# Dashboard.net
KiCad netlist of a schematic drawn in Altium Designer
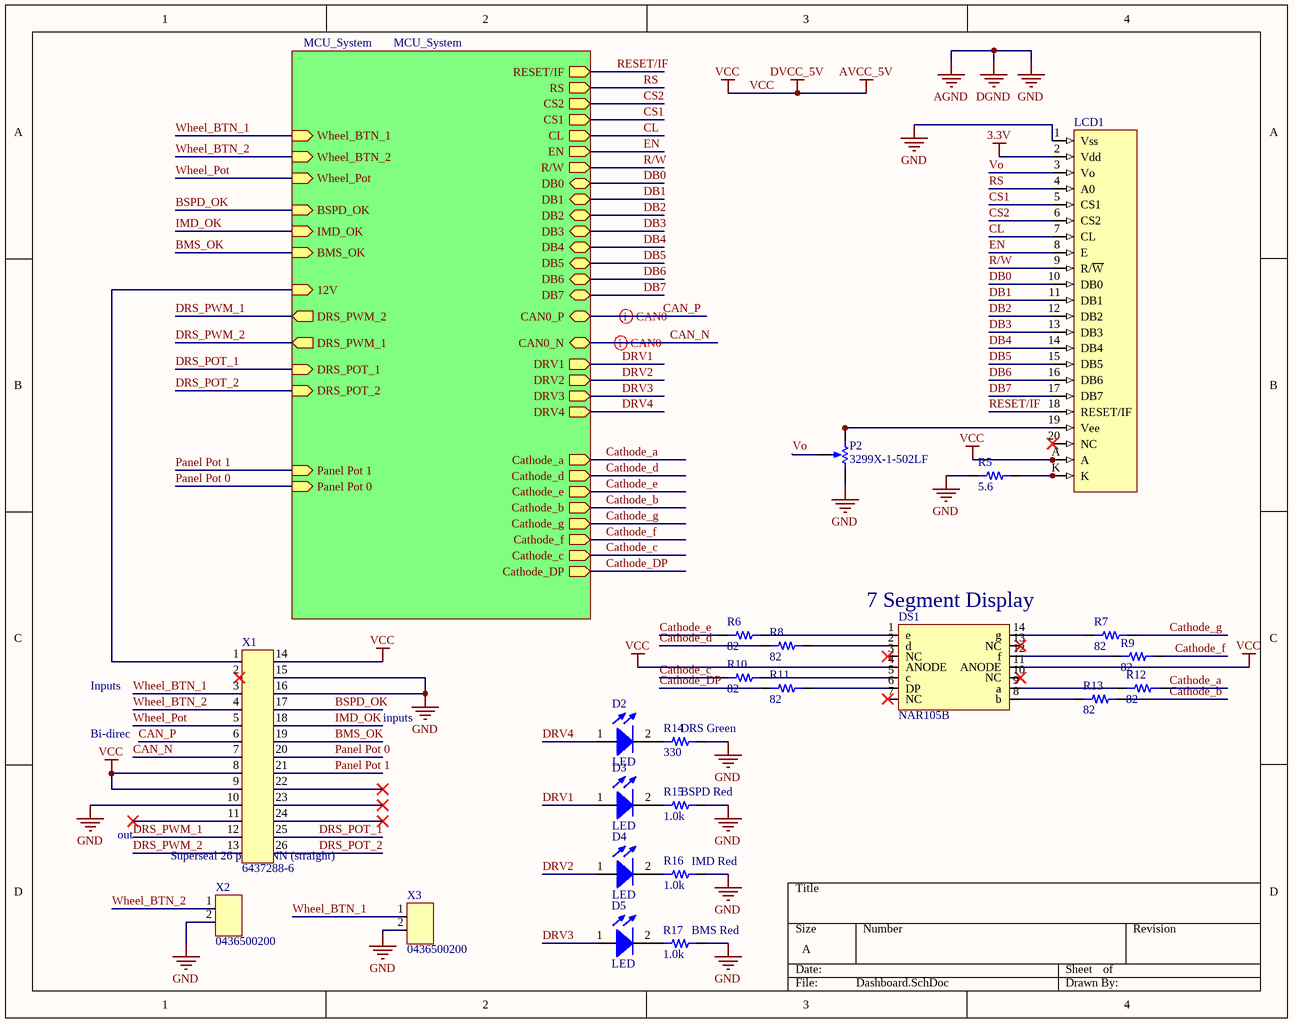
[diagram p0: Dashboard.SchDoc]

(export (version "E")
  (design (tool "Eeschema 10.0.6"))
  (components
    (comp (ref "D2")
      (value "LED")
      (footprint "LED TH")
      (description "LED GREEN DIFFUSED T/H")
      (fields (field (name "MFRPARTNO") "LTL-10233W"))
      (libsource (lib "Altium-Lib") (part "LED"))
    )
    (comp (ref "D3")
      (value "LED")
      (footprint "LED TH")
      (description "LED RED DIFFUSED T/H")
      (fields (field (name "MFRPARTNO") "LTL2R3KRD-EM"))
      (libsource (lib "Altium-Lib") (part "LED"))
    )
    (comp (ref "D4")
      (value "LED")
      (footprint "LED TH")
      (description "LED RED DIFFUSED T/H")
      (fields (field (name "MFRPARTNO") "LTL2R3KRD-EM"))
      (libsource (lib "Altium-Lib") (part "LED"))
    )
    (comp (ref "D5")
      (value "LED")
      (footprint "LED TH")
      (description "LED RED DIFFUSED T/H")
      (fields (field (name "MFRPARTNO") "LTL2R3KRD-EM"))
      (libsource (lib "Altium-Lib") (part "LED"))
    )
    (comp (ref "DS1")
      (value "NAR105B")
      (footprint "Stanley7Seg")
      (libsource (lib "Altium-Lib") (part "Stanley7Seg"))
    )
    (comp (ref "LCD1")
      (value "~")
      (footprint "NHD-12232")
      (fields (field (name "MFRPARTNO") "NHD-12232WG-EYYH-V#A-ND"))
      (libsource (lib "Altium-Lib") (part "NHD-12232"))
    )
    (comp (ref "P2")
      (value "3299X-1-502LF")
      (footprint "3299X-1-502LF")
      (libsource (lib "Altium-Lib") (part "3299X-1-502LF"))
    )
    (comp (ref "R5")
      (value "5.6")
      (footprint "RES 0805/2012")
      (fields
        (field (name "TOLERANCE") "1%")
        (field (name "POWER") "1/2W")
        (field (name "Comment") "Resistor 5.6 0805 1/2W 1%")
        (field (name "CREATED_BY") "Nick Mah")
      )
      (libsource (lib "Altium-Lib") (part "Resistor"))
    )
    (comp (ref "R6")
      (value "82")
      (footprint "RES 0805/2012")
      (fields
        (field (name "TOLERANCE") "5%")
        (field (name "POWER") "1/4W")
        (field (name "Comment") "Resistor 82 0805 1/4W 5%")
        (field (name "CREATED_BY") "Nick Mah")
      )
      (libsource (lib "Altium-Lib") (part "Resistor"))
    )
    (comp (ref "R7")
      (value "82")
      (footprint "RES 0805/2012")
      (fields
        (field (name "TOLERANCE") "5%")
        (field (name "POWER") "1/4W")
        (field (name "Comment") "Resistor 82 0805 1/4W 5%")
        (field (name "CREATED_BY") "Nick Mah")
      )
      (libsource (lib "Altium-Lib") (part "Resistor"))
    )
    (comp (ref "R8")
      (value "82")
      (footprint "RES 0805/2012")
      (fields
        (field (name "TOLERANCE") "5%")
        (field (name "POWER") "1/4W")
        (field (name "Comment") "Resistor 82 0805 1/4W 5%")
        (field (name "CREATED_BY") "Nick Mah")
      )
      (libsource (lib "Altium-Lib") (part "Resistor"))
    )
    (comp (ref "R9")
      (value "82")
      (footprint "RES 0805/2012")
      (fields
        (field (name "TOLERANCE") "5%")
        (field (name "POWER") "1/4W")
        (field (name "Comment") "Resistor 82 0805 1/4W 5%")
        (field (name "CREATED_BY") "Nick Mah")
      )
      (libsource (lib "Altium-Lib") (part "Resistor"))
    )
    (comp (ref "R10")
      (value "82")
      (footprint "RES 0805/2012")
      (fields
        (field (name "TOLERANCE") "5%")
        (field (name "POWER") "1/4W")
        (field (name "Comment") "Resistor 82 0805 1/4W 5%")
        (field (name "CREATED_BY") "Nick Mah")
      )
      (libsource (lib "Altium-Lib") (part "Resistor"))
    )
    (comp (ref "R11")
      (value "82")
      (footprint "RES 0805/2012")
      (fields
        (field (name "TOLERANCE") "5%")
        (field (name "POWER") "1/4W")
        (field (name "Comment") "Resistor 82 0805 1/4W 5%")
        (field (name "CREATED_BY") "Nick Mah")
      )
      (libsource (lib "Altium-Lib") (part "Resistor"))
    )
    (comp (ref "R12")
      (value "82")
      (footprint "RES 0805/2012")
      (fields
        (field (name "TOLERANCE") "5%")
        (field (name "POWER") "1/4W")
        (field (name "Comment") "Resistor 82 0805 1/4W 5%")
        (field (name "CREATED_BY") "Nick Mah")
      )
      (libsource (lib "Altium-Lib") (part "Resistor"))
    )
    (comp (ref "R13")
      (value "82")
      (footprint "RES 0805/2012")
      (fields
        (field (name "TOLERANCE") "5%")
        (field (name "POWER") "1/4W")
        (field (name "Comment") "Resistor 82 0805 1/4W 5%")
        (field (name "CREATED_BY") "Nick Mah")
      )
      (libsource (lib "Altium-Lib") (part "Resistor"))
    )
    (comp (ref "R14")
      (value "330")
      (footprint "RES 0805/2012")
      (fields
        (field (name "TOLERANCE") "5%")
        (field (name "POWER") "1/4W")
        (field (name "Comment") "Resistor 330 0805 1/4W 5%")
        (field (name "CREATED_BY") "Nick Mah")
      )
      (libsource (lib "Altium-Lib") (part "Resistor"))
    )
    (comp (ref "R15")
      (value "1.0k")
      (footprint "RES 0805/2012")
      (fields
        (field (name "TOLERANCE") "5%")
        (field (name "POWER") "1/4W")
        (field (name "Comment") "Resistor 1.0k 0805 1/4W 5%")
        (field (name "CREATED_BY") "Nick Mah")
      )
      (libsource (lib "Altium-Lib") (part "Resistor"))
    )
    (comp (ref "R16")
      (value "1.0k")
      (footprint "RES 0805/2012")
      (fields
        (field (name "TOLERANCE") "5%")
        (field (name "POWER") "1/4W")
        (field (name "Comment") "Resistor 1.0k 0805 1/4W 5%")
        (field (name "CREATED_BY") "Nick Mah")
      )
      (libsource (lib "Altium-Lib") (part "Resistor"))
    )
    (comp (ref "R17")
      (value "1.0k")
      (footprint "RES 0805/2012")
      (fields
        (field (name "TOLERANCE") "5%")
        (field (name "POWER") "1/4W")
        (field (name "Comment") "Resistor 1.0k 0805 1/4W 5%")
        (field (name "CREATED_BY") "Nick Mah")
      )
      (libsource (lib "Altium-Lib") (part "Resistor"))
    )
    (comp (ref "X1")
      (value "6437288-6")
      (footprint "TE_Amp_6437288-6")
      (description "Straight Angle 26Pos AMPSeal")
      (fields (field (name "CREATED_BY") "Nick"))
      (libsource (lib "Altium-Lib") (part "CONN 26POS"))
    )
    (comp (ref "X2")
      (value "0436500200")
      (footprint "CONN 43650-0200 MOLEX 2PIN")
      (fields (field (name "CREATED_BY") "Nick"))
      (libsource (lib "Altium-Lib") (part "CONN 2POS"))
    )
    (comp (ref "X3")
      (value "0436500200")
      (footprint "CONN 43650-0200 MOLEX 2PIN")
      (fields (field (name "CREATED_BY") "Nick"))
      (libsource (lib "Altium-Lib") (part "CONN 2POS"))
    )
  )
  (nets
    (net (code "1") (name "/12V") (class "Default") (node (ref "X1") (pin "1") (pintype "input")))
    (net (code "3") (name "/BMS_OK") (class "Default") (node (ref "X1") (pin "19") (pintype "input")))
    (net (code "4") (name "/BSPD_OK") (class "Default") (node (ref "X1") (pin "17") (pintype "input")))
    (net (code "5") (name "/CAN_N") (class "Default") (node (ref "X1") (pin "7") (pintype "input")))
    (net (code "6") (name "/CAN_P") (class "Default") (node (ref "X1") (pin "6") (pintype "input")))
    (net (code "7") (name "/CL") (class "Default")
      (node (ref "LCD1") (pin "7") (pinfunction "CL_7") (pintype "input"))
    )
    (net (code "8") (name "/CS1") (class "Default")
      (node (ref "LCD1") (pin "5") (pinfunction "CS1_5") (pintype "input"))
    )
    (net (code "9") (name "/CS2") (class "Default")
      (node (ref "LCD1") (pin "6") (pinfunction "CS2_6") (pintype "input"))
    )
    (net (code "10") (name "/Cathode_DP") (class "Default")
      (node (ref "R11") (pin "1") (pinfunction "1_1") (pintype "passive"))
    )
    (net (code "11") (name "/Cathode_a") (class "Default")
      (node (ref "R12") (pin "2") (pinfunction "2_2") (pintype "passive"))
    )
    (net (code "12") (name "/Cathode_b") (class "Default")
      (node (ref "R13") (pin "2") (pinfunction "2_2") (pintype "passive"))
    )
    (net (code "13") (name "/Cathode_c") (class "Default")
      (node (ref "R10") (pin "1") (pinfunction "1_1") (pintype "passive"))
    )
    (net (code "14") (name "/Cathode_d") (class "Default")
      (node (ref "R8") (pin "1") (pinfunction "1_1") (pintype "passive"))
    )
    (net (code "15") (name "/Cathode_e") (class "Default")
      (node (ref "R6") (pin "1") (pinfunction "1_1") (pintype "passive"))
    )
    (net (code "16") (name "/Cathode_f") (class "Default")
      (node (ref "R9") (pin "2") (pinfunction "2_2") (pintype "passive"))
    )
    (net (code "17") (name "/Cathode_g") (class "Default")
      (node (ref "R7") (pin "2") (pinfunction "2_2") (pintype "passive"))
    )
    (net (code "18") (name "/DB0") (class "Default")
      (node (ref "LCD1") (pin "10") (pinfunction "DB0_10") (pintype "input"))
    )
    (net (code "19") (name "/DB1") (class "Default")
      (node (ref "LCD1") (pin "11") (pinfunction "DB1_11") (pintype "input"))
    )
    (net (code "20") (name "/DB2") (class "Default")
      (node (ref "LCD1") (pin "12") (pinfunction "DB2_12") (pintype "input"))
    )
    (net (code "21") (name "/DB3") (class "Default")
      (node (ref "LCD1") (pin "13") (pinfunction "DB3_13") (pintype "input"))
    )
    (net (code "22") (name "/DB4") (class "Default")
      (node (ref "LCD1") (pin "14") (pinfunction "DB4_14") (pintype "input"))
    )
    (net (code "23") (name "/DB5") (class "Default")
      (node (ref "LCD1") (pin "15") (pinfunction "DB5_15") (pintype "input"))
    )
    (net (code "24") (name "/DB6") (class "Default")
      (node (ref "LCD1") (pin "16") (pinfunction "DB6_16") (pintype "input"))
    )
    (net (code "25") (name "/DB7") (class "Default")
      (node (ref "LCD1") (pin "17") (pinfunction "DB7_17") (pintype "input"))
    )
    (net (code "26") (name "/DRS_POT_1") (class "Default") (node (ref "X1") (pin "25") (pintype "input")))
    (net (code "27") (name "/DRS_POT_2") (class "Default") (node (ref "X1") (pin "26") (pintype "input")))
    (net (code "28") (name "/DRS_PWM_1") (class "Default") (node (ref "X1") (pin "12") (pintype "input")))
    (net (code "29") (name "/DRS_PWM_2") (class "Default") (node (ref "X1") (pin "13") (pintype "input")))
    (net (code "30") (name "/DRV1") (class "Default")
      (node (ref "D3") (pin "1") (pinfunction "A_1") (pintype "passive"))
    )
    (net (code "31") (name "/DRV2") (class "Default")
      (node (ref "D4") (pin "1") (pinfunction "A_1") (pintype "passive"))
    )
    (net (code "32") (name "/DRV3") (class "Default")
      (node (ref "D5") (pin "1") (pinfunction "A_1") (pintype "passive"))
    )
    (net (code "33") (name "/DRV4") (class "Default")
      (node (ref "D2") (pin "1") (pinfunction "A_1") (pintype "passive"))
    )
    (net (code "34") (name "/EN") (class "Default")
      (node (ref "LCD1") (pin "8") (pinfunction "E_8") (pintype "input"))
    )
    (net (code "35") (name "/IMD_OK") (class "Default") (node (ref "X1") (pin "18") (pintype "input")))
    (net (code "36") (name "/Panel Pot 0") (class "Default") (node (ref "X1") (pin "20") (pintype "input")))
    (net (code "37") (name "/Panel Pot 1") (class "Default") (node (ref "X1") (pin "21") (pintype "input")))
    (net (code "38") (name "/RESET{slash}IF") (class "Default")
      (node (ref "LCD1") (pin "18") (pinfunction "RESET/IF_18") (pintype "input"))
    )
    (net (code "39") (name "/RS") (class "Default")
      (node (ref "LCD1") (pin "4") (pinfunction "A0_4") (pintype "input"))
    )
    (net (code "40") (name "/R{slash}W") (class "Default")
      (node (ref "LCD1") (pin "9") (pinfunction "R/~{W}_9") (pintype "input"))
    )
    (net (code "41") (name "/Vo") (class "Default")
      (node (ref "LCD1") (pin "3") (pinfunction "Vo_3") (pintype "input"))
      (node (ref "P2") (pin "2") (pinfunction "TAP_2") (pintype "passive"))
    )
    (net (code "42") (name "/Wheel_BTN_1") (class "Default")
      (node (ref "X1") (pin "3") (pintype "input"))
      (node (ref "X3") (pin "1") (pintype "input"))
    )
    (net (code "43") (name "/Wheel_BTN_2") (class "Default")
      (node (ref "X1") (pin "4") (pintype "input"))
      (node (ref "X2") (pin "1") (pintype "input"))
    )
    (net (code "44") (name "/Wheel_Pot") (class "Default") (node (ref "X1") (pin "5") (pintype "input")))
    (net (code "45") (name "3.3V") (class "Default")
      (node (ref "LCD1") (pin "2") (pinfunction "Vdd_2") (pintype "input"))
    )
    (net (code "46") (name "AGND") (class "Default")
      (node (ref "LCD1") (pin "1") (pinfunction "Vss_1") (pintype "input"))
      (node (ref "P2") (pin "3") (pinfunction "BOT_3") (pintype "passive"))
      (node (ref "R14") (pin "2") (pinfunction "2_2") (pintype "passive"))
      (node (ref "R15") (pin "2") (pinfunction "2_2") (pintype "passive"))
      (node (ref "R16") (pin "2") (pinfunction "2_2") (pintype "passive"))
      (node (ref "R17") (pin "2") (pinfunction "2_2") (pintype "passive"))
      (node (ref "R5") (pin "1") (pinfunction "1_1") (pintype "passive"))
      (node (ref "X1") (pin "10") (pintype "input"))
      (node (ref "X1") (pin "15") (pintype "input"))
      (node (ref "X1") (pin "16") (pintype "input"))
      (node (ref "X2") (pin "2") (pintype "input"))
      (node (ref "X3") (pin "2") (pintype "input"))
    )
    (net (code "47") (name "AVCC_5V") (class "Default")
      (node (ref "DS1") (pin "11") (pinfunction "ANODE_11") (pintype "passive"))
      (node (ref "DS1") (pin "4") (pinfunction "ANODE_4") (pintype "passive"))
      (node (ref "LCD1") (pin "A") (pinfunction "A_A") (pintype "input"))
      (node (ref "LCD1") (pin "A2") (pinfunction "A_A2") (pintype "input"))
      (node (ref "X1") (pin "14") (pintype "input"))
      (node (ref "X1") (pin "8") (pintype "input"))
      (node (ref "X1") (pin "9") (pintype "input"))
    )
    (net (code "48") (name "Net-(D2-K)") (class "Default")
      (node (ref "D2") (pin "2") (pinfunction "K_2") (pintype "passive"))
      (node (ref "R14") (pin "1") (pinfunction "1_1") (pintype "passive"))
    )
    (net (code "49") (name "Net-(D3-K)") (class "Default")
      (node (ref "D3") (pin "2") (pinfunction "K_2") (pintype "passive"))
      (node (ref "R15") (pin "1") (pinfunction "1_1") (pintype "passive"))
    )
    (net (code "50") (name "Net-(D4-K)") (class "Default")
      (node (ref "D4") (pin "2") (pinfunction "K_2") (pintype "passive"))
      (node (ref "R16") (pin "1") (pinfunction "1_1") (pintype "passive"))
    )
    (net (code "51") (name "Net-(D5-K)") (class "Default")
      (node (ref "D5") (pin "2") (pinfunction "K_2") (pintype "passive"))
      (node (ref "R17") (pin "1") (pinfunction "1_1") (pintype "passive"))
    )
    (net (code "52") (name "Net-(DS1-DP)") (class "Default")
      (node (ref "DS1") (pin "6") (pinfunction "DP_6") (pintype "passive"))
      (node (ref "R11") (pin "2") (pinfunction "2_2") (pintype "passive"))
    )
    (net (code "53") (name "Net-(DS1-a)") (class "Default")
      (node (ref "DS1") (pin "9") (pinfunction "a_9") (pintype "passive"))
      (node (ref "R12") (pin "1") (pinfunction "1_1") (pintype "passive"))
    )
    (net (code "54") (name "Net-(DS1-b)") (class "Default")
      (node (ref "DS1") (pin "8") (pinfunction "b_8") (pintype "passive"))
      (node (ref "R13") (pin "1") (pinfunction "1_1") (pintype "passive"))
    )
    (net (code "55") (name "Net-(DS1-c)") (class "Default")
      (node (ref "DS1") (pin "5") (pinfunction "c_5") (pintype "passive"))
      (node (ref "R10") (pin "2") (pinfunction "2_2") (pintype "passive"))
    )
    (net (code "56") (name "Net-(DS1-d)") (class "Default")
      (node (ref "DS1") (pin "2") (pinfunction "d_2") (pintype "passive"))
      (node (ref "R8") (pin "2") (pinfunction "2_2") (pintype "passive"))
    )
    (net (code "57") (name "Net-(DS1-e)") (class "Default")
      (node (ref "DS1") (pin "1") (pinfunction "e_1") (pintype "passive"))
      (node (ref "R6") (pin "2") (pinfunction "2_2") (pintype "passive"))
    )
    (net (code "58") (name "Net-(DS1-f)") (class "Default")
      (node (ref "DS1") (pin "12") (pinfunction "f_12") (pintype "passive"))
      (node (ref "R9") (pin "1") (pinfunction "1_1") (pintype "passive"))
    )
    (net (code "59") (name "Net-(DS1-g)") (class "Default")
      (node (ref "DS1") (pin "14") (pinfunction "g_14") (pintype "passive"))
      (node (ref "R7") (pin "1") (pinfunction "1_1") (pintype "passive"))
    )
    (net (code "60") (name "Net-(LCD1-K-PadK2)") (class "Default")
      (node (ref "LCD1") (pin "K") (pinfunction "K_K") (pintype "input"))
      (node (ref "LCD1") (pin "K2") (pinfunction "K_K2") (pintype "input"))
      (node (ref "R5") (pin "2") (pinfunction "2_2") (pintype "passive"))
    )
    (net (code "61") (name "Net-(LCD1-Vee)") (class "Default")
      (node (ref "LCD1") (pin "19") (pinfunction "Vee_19") (pintype "input"))
      (node (ref "P2") (pin "1") (pinfunction "TOP_1") (pintype "passive"))
    )
    (net (code "62") (name "unconnected-(DS1-NC-Pad3)") (class "Default")
      (node (ref "DS1") (pin "3") (pinfunction "NC_3") (pintype "passive+no_connect"))
    )
    (net (code "63") (name "unconnected-(DS1-NC-Pad7)") (class "Default")
      (node (ref "DS1") (pin "7") (pinfunction "NC_7") (pintype "passive+no_connect"))
    )
    (net (code "64") (name "unconnected-(DS1-NC-Pad10)") (class "Default")
      (node (ref "DS1") (pin "10") (pinfunction "NC_10") (pintype "passive+no_connect"))
    )
    (net (code "65") (name "unconnected-(DS1-NC-Pad13)") (class "Default")
      (node (ref "DS1") (pin "13") (pinfunction "NC_13") (pintype "passive+no_connect"))
    )
    (net (code "66") (name "unconnected-(LCD1-NC-Pad20)") (class "Default")
      (node (ref "LCD1") (pin "20") (pinfunction "NC_20") (pintype "input+no_connect"))
    )
    (net (code "67") (name "unconnected-(X1-Pad2)") (class "Default")
      (node (ref "X1") (pin "2") (pintype "input+no_connect"))
    )
    (net (code "68") (name "unconnected-(X1-Pad11)") (class "Default")
      (node (ref "X1") (pin "11") (pintype "input+no_connect"))
    )
    (net (code "69") (name "unconnected-(X1-Pad22)") (class "Default")
      (node (ref "X1") (pin "22") (pintype "input+no_connect"))
    )
    (net (code "70") (name "unconnected-(X1-Pad23)") (class "Default")
      (node (ref "X1") (pin "23") (pintype "input+no_connect"))
    )
    (net (code "71") (name "unconnected-(X1-Pad24)") (class "Default")
      (node (ref "X1") (pin "24") (pintype "input+no_connect"))
    )
  )
)
